# BMS.net
KiCad netlist of a schematic drawn in EAGLE
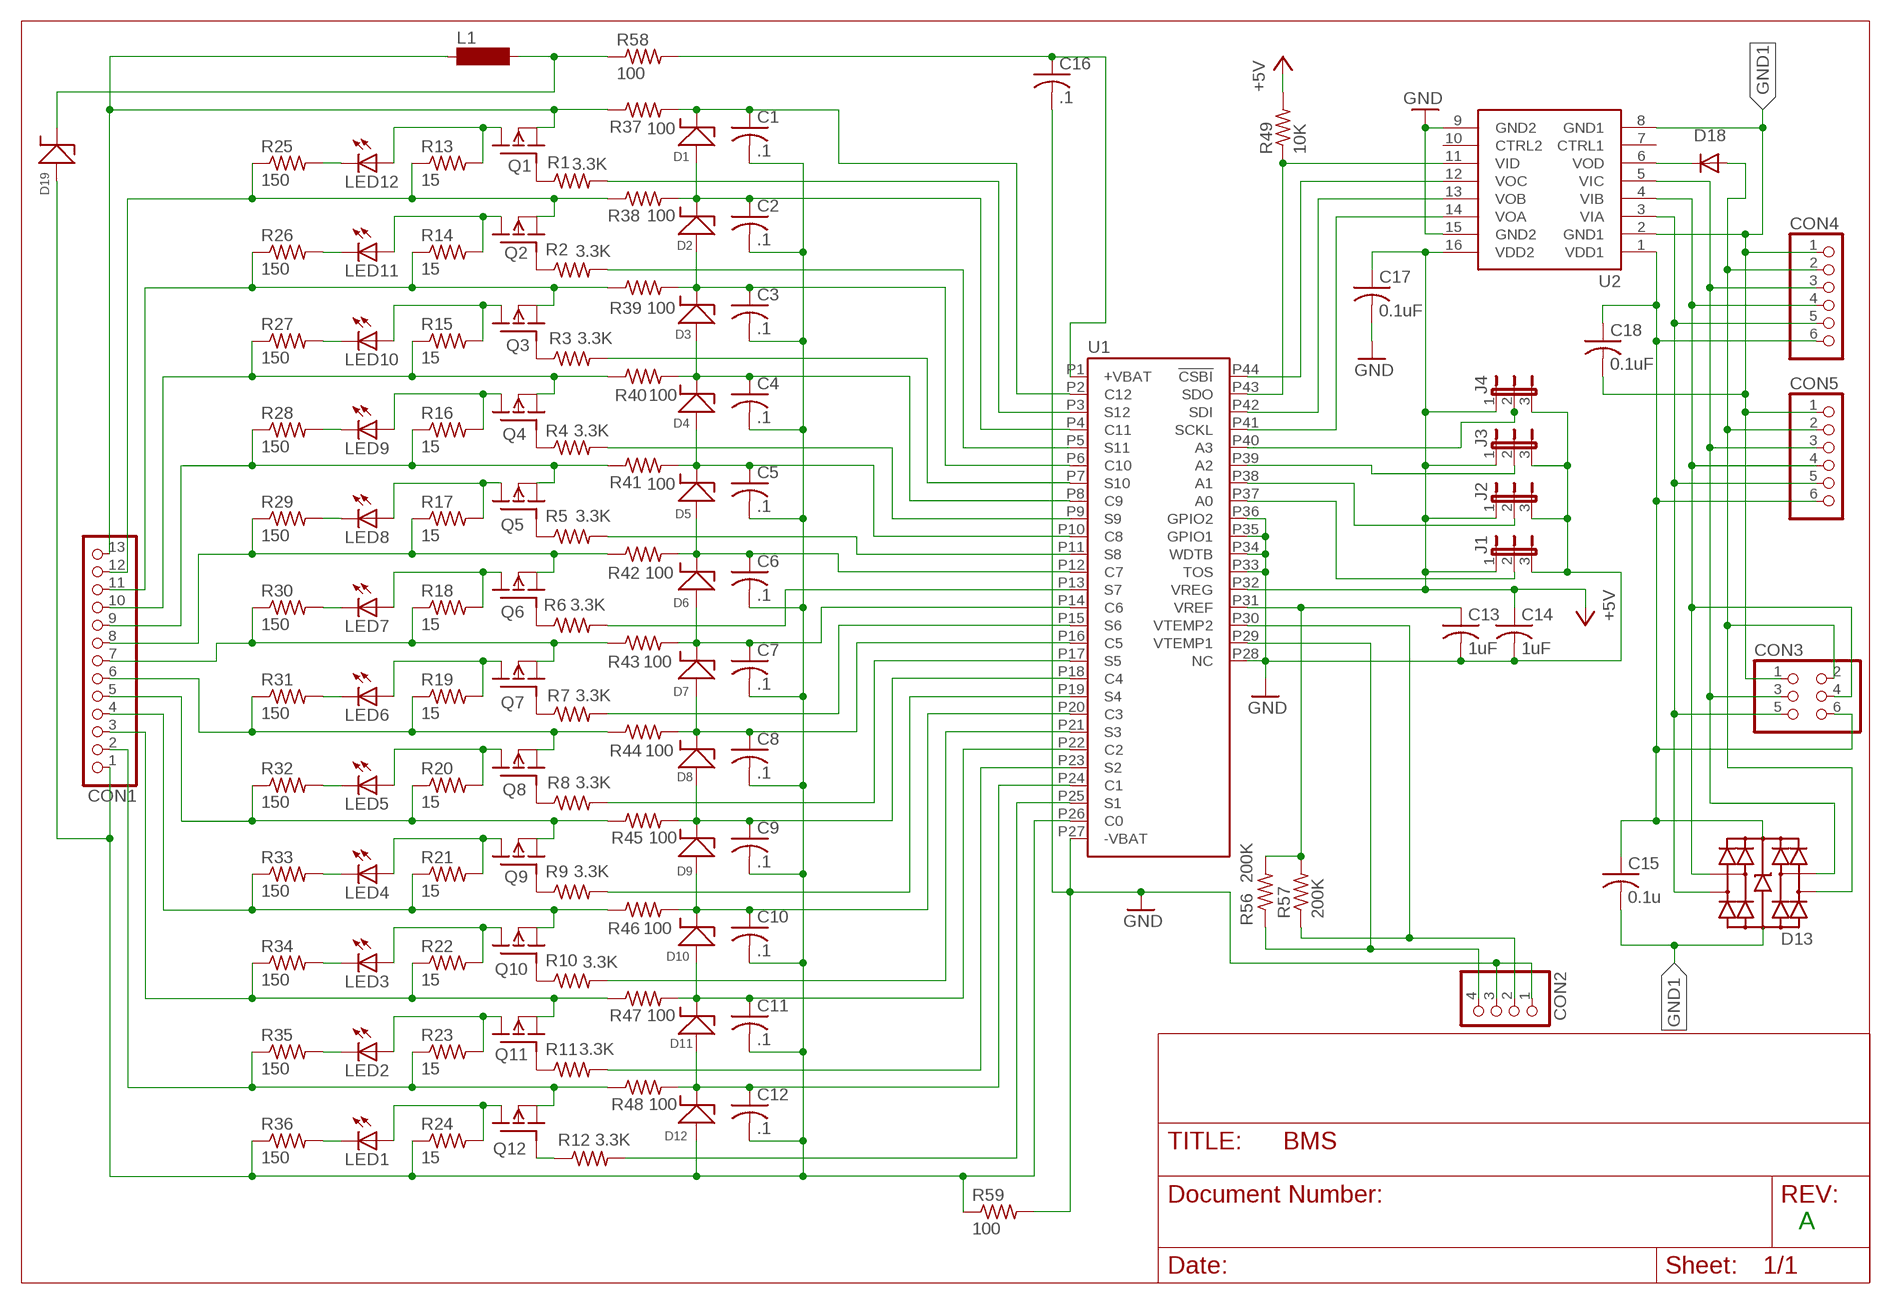
[diagram p0: schematic, sheet 1]

(export (version "E")
  (design (tool "Eeschema 10.0.6"))
  (components
    (comp (ref "C1")
      (value ".1")
      (footprint "eagle-import:C0603")
      (libsource (lib "eagle-import") (part "C-USC0603"))
    )
    (comp (ref "C2")
      (value ".1")
      (footprint "eagle-import:C0603")
      (libsource (lib "eagle-import") (part "C-USC0603"))
    )
    (comp (ref "C3")
      (value ".1")
      (footprint "eagle-import:C0603")
      (libsource (lib "eagle-import") (part "C-USC0603"))
    )
    (comp (ref "C4")
      (value ".1")
      (footprint "eagle-import:C0603")
      (libsource (lib "eagle-import") (part "C-USC0603"))
    )
    (comp (ref "C5")
      (value ".1")
      (footprint "eagle-import:C0603")
      (libsource (lib "eagle-import") (part "C-USC0603"))
    )
    (comp (ref "C6")
      (value ".1")
      (footprint "eagle-import:C0603")
      (libsource (lib "eagle-import") (part "C-USC0603"))
    )
    (comp (ref "C7")
      (value ".1")
      (footprint "eagle-import:C0603")
      (libsource (lib "eagle-import") (part "C-USC0603"))
    )
    (comp (ref "C8")
      (value ".1")
      (footprint "eagle-import:C0603")
      (libsource (lib "eagle-import") (part "C-USC0603"))
    )
    (comp (ref "C9")
      (value ".1")
      (footprint "eagle-import:C0603")
      (libsource (lib "eagle-import") (part "C-USC0603"))
    )
    (comp (ref "C10")
      (value ".1")
      (footprint "eagle-import:C0603")
      (libsource (lib "eagle-import") (part "C-USC0603"))
    )
    (comp (ref "C11")
      (value ".1")
      (footprint "eagle-import:C0603")
      (libsource (lib "eagle-import") (part "C-USC0603"))
    )
    (comp (ref "C12")
      (value ".1")
      (footprint "eagle-import:C0603")
      (libsource (lib "eagle-import") (part "C-USC0603"))
    )
    (comp (ref "C13")
      (value "1uF")
      (footprint "eagle-import:C0603")
      (libsource (lib "eagle-import") (part "C-USC0603"))
    )
    (comp (ref "C14")
      (value "1uF")
      (footprint "eagle-import:C0603")
      (libsource (lib "eagle-import") (part "C-USC0603"))
    )
    (comp (ref "C15")
      (value "0.1u")
      (footprint "eagle-import:C0603")
      (libsource (lib "eagle-import") (part "C-USC0603"))
    )
    (comp (ref "C16")
      (value ".1")
      (footprint "eagle-import:C0603")
      (libsource (lib "eagle-import") (part "C-USC0603"))
    )
    (comp (ref "C17")
      (value "0.1uF")
      (footprint "eagle-import:C0603")
      (libsource (lib "eagle-import") (part "C-USC0603"))
    )
    (comp (ref "C18")
      (value "0.1uF")
      (footprint "eagle-import:C0603")
      (libsource (lib "eagle-import") (part "C-USC0603"))
    )
    (comp (ref "CON1")
      (value "PINHD-1X13/90")
      (footprint "eagle-import:1X13_90")
      (libsource (lib "eagle-import") (part "PINHD-1X13/90"))
    )
    (comp (ref "CON2")
      (value "PINHD-1X4/90")
      (footprint "eagle-import:1X04_90")
      (libsource (lib "eagle-import") (part "PINHD-1X4/90"))
    )
    (comp (ref "CON3")
      (value "PINHD-2X3/90")
      (footprint "eagle-import:2X03_90")
      (libsource (lib "eagle-import") (part "PINHD-2X3/90"))
    )
    (comp (ref "CON4")
      (value "PINHD-1X6/90")
      (footprint "eagle-import:1X06_90")
      (libsource (lib "eagle-import") (part "PINHD-1X6/90"))
    )
    (comp (ref "CON5")
      (value "PINHD-1X6/90")
      (footprint "eagle-import:1X06_90")
      (libsource (lib "eagle-import") (part "PINHD-1X6/90"))
    )
    (comp (ref "D1")
      (value "PDZ7.5B")
      (footprint "eagle-import:SOD323")
      (libsource (lib "eagle-import") (part "PDZ7.5B"))
    )
    (comp (ref "D2")
      (value "PDZ7.5B")
      (footprint "eagle-import:SOD323")
      (libsource (lib "eagle-import") (part "PDZ7.5B"))
    )
    (comp (ref "D3")
      (value "PDZ7.5B")
      (footprint "eagle-import:SOD323")
      (libsource (lib "eagle-import") (part "PDZ7.5B"))
    )
    (comp (ref "D4")
      (value "PDZ7.5B")
      (footprint "eagle-import:SOD323")
      (libsource (lib "eagle-import") (part "PDZ7.5B"))
    )
    (comp (ref "D5")
      (value "PDZ7.5B")
      (footprint "eagle-import:SOD323")
      (libsource (lib "eagle-import") (part "PDZ7.5B"))
    )
    (comp (ref "D6")
      (value "PDZ7.5B")
      (footprint "eagle-import:SOD323")
      (libsource (lib "eagle-import") (part "PDZ7.5B"))
    )
    (comp (ref "D7")
      (value "PDZ7.5B")
      (footprint "eagle-import:SOD323")
      (libsource (lib "eagle-import") (part "PDZ7.5B"))
    )
    (comp (ref "D8")
      (value "PDZ7.5B")
      (footprint "eagle-import:SOD323")
      (libsource (lib "eagle-import") (part "PDZ7.5B"))
    )
    (comp (ref "D9")
      (value "PDZ7.5B")
      (footprint "eagle-import:SOD323")
      (libsource (lib "eagle-import") (part "PDZ7.5B"))
    )
    (comp (ref "D10")
      (value "PDZ7.5B")
      (footprint "eagle-import:SOD323")
      (libsource (lib "eagle-import") (part "PDZ7.5B"))
    )
    (comp (ref "D11")
      (value "PDZ7.5B")
      (footprint "eagle-import:SOD323")
      (libsource (lib "eagle-import") (part "PDZ7.5B"))
    )
    (comp (ref "D12")
      (value "PDZ7.5B")
      (footprint "eagle-import:SOD323")
      (libsource (lib "eagle-import") (part "PDZ7.5B"))
    )
    (comp (ref "D13")
      (value "TPD4E001DBV")
      (footprint "eagle-import:SOT23-6")
      (libsource (lib "eagle-import") (part "TPD4E001DBV"))
    )
    (comp (ref "D18")
      (value "DIODE0603")
      (footprint "eagle-import:LED-0603")
      (libsource (lib "eagle-import") (part "DIODE0603"))
    )
    (comp (ref "D19")
      (value "MMSZ5265BTIG")
      (footprint "eagle-import:SOD-123_MINI-SMA")
      (libsource (lib "eagle-import") (part "MMSZ5265BTIG"))
    )
    (comp (ref "J1")
      (value "JP2E")
      (footprint "eagle-import:JP2")
      (libsource (lib "eagle-import") (part "JP2E"))
    )
    (comp (ref "J2")
      (value "JP2E")
      (footprint "eagle-import:JP2")
      (libsource (lib "eagle-import") (part "JP2E"))
    )
    (comp (ref "J3")
      (value "JP2E")
      (footprint "eagle-import:JP2")
      (libsource (lib "eagle-import") (part "JP2E"))
    )
    (comp (ref "J4")
      (value "JP2E")
      (footprint "eagle-import:JP2")
      (libsource (lib "eagle-import") (part "JP2E"))
    )
    (comp (ref "L1")
      (value "CHOKE")
      (footprint "eagle-import:CHOKE1206")
      (libsource (lib "eagle-import") (part "CHOKE"))
    )
    (comp (ref "LED1")
      (value "LED0603")
      (footprint "eagle-import:LED-0603")
      (libsource (lib "eagle-import") (part "LED0603"))
    )
    (comp (ref "LED2")
      (value "LED0603")
      (footprint "eagle-import:LED-0603")
      (libsource (lib "eagle-import") (part "LED0603"))
    )
    (comp (ref "LED3")
      (value "LED0603")
      (footprint "eagle-import:LED-0603")
      (libsource (lib "eagle-import") (part "LED0603"))
    )
    (comp (ref "LED4")
      (value "LED0603")
      (footprint "eagle-import:LED-0603")
      (libsource (lib "eagle-import") (part "LED0603"))
    )
    (comp (ref "LED5")
      (value "LED0603")
      (footprint "eagle-import:LED-0603")
      (libsource (lib "eagle-import") (part "LED0603"))
    )
    (comp (ref "LED6")
      (value "LED0603")
      (footprint "eagle-import:LED-0603")
      (libsource (lib "eagle-import") (part "LED0603"))
    )
    (comp (ref "LED7")
      (value "LED0603")
      (footprint "eagle-import:LED-0603")
      (libsource (lib "eagle-import") (part "LED0603"))
    )
    (comp (ref "LED8")
      (value "LED0603")
      (footprint "eagle-import:LED-0603")
      (libsource (lib "eagle-import") (part "LED0603"))
    )
    (comp (ref "LED9")
      (value "LED0603")
      (footprint "eagle-import:LED-0603")
      (libsource (lib "eagle-import") (part "LED0603"))
    )
    (comp (ref "LED10")
      (value "LED0603")
      (footprint "eagle-import:LED-0603")
      (libsource (lib "eagle-import") (part "LED0603"))
    )
    (comp (ref "LED11")
      (value "LED0603")
      (footprint "eagle-import:LED-0603")
      (libsource (lib "eagle-import") (part "LED0603"))
    )
    (comp (ref "LED12")
      (value "LED0603")
      (footprint "eagle-import:LED-0603")
      (libsource (lib "eagle-import") (part "LED0603"))
    )
    (comp (ref "Q1")
      (value "FDY102PZ")
      (footprint "eagle-import:SC89-3")
      (libsource (lib "eagle-import") (part "FDY102PZ"))
    )
    (comp (ref "Q2")
      (value "FDY102PZ")
      (footprint "eagle-import:SC89-3")
      (libsource (lib "eagle-import") (part "FDY102PZ"))
    )
    (comp (ref "Q3")
      (value "FDY102PZ")
      (footprint "eagle-import:SC89-3")
      (libsource (lib "eagle-import") (part "FDY102PZ"))
    )
    (comp (ref "Q4")
      (value "FDY102PZ")
      (footprint "eagle-import:SC89-3")
      (libsource (lib "eagle-import") (part "FDY102PZ"))
    )
    (comp (ref "Q5")
      (value "FDY102PZ")
      (footprint "eagle-import:SC89-3")
      (libsource (lib "eagle-import") (part "FDY102PZ"))
    )
    (comp (ref "Q6")
      (value "FDY102PZ")
      (footprint "eagle-import:SC89-3")
      (libsource (lib "eagle-import") (part "FDY102PZ"))
    )
    (comp (ref "Q7")
      (value "FDY102PZ")
      (footprint "eagle-import:SC89-3")
      (libsource (lib "eagle-import") (part "FDY102PZ"))
    )
    (comp (ref "Q8")
      (value "FDY102PZ")
      (footprint "eagle-import:SC89-3")
      (libsource (lib "eagle-import") (part "FDY102PZ"))
    )
    (comp (ref "Q9")
      (value "FDY102PZ")
      (footprint "eagle-import:SC89-3")
      (libsource (lib "eagle-import") (part "FDY102PZ"))
    )
    (comp (ref "Q10")
      (value "FDY102PZ")
      (footprint "eagle-import:SC89-3")
      (libsource (lib "eagle-import") (part "FDY102PZ"))
    )
    (comp (ref "Q11")
      (value "FDY102PZ")
      (footprint "eagle-import:SC89-3")
      (libsource (lib "eagle-import") (part "FDY102PZ"))
    )
    (comp (ref "Q12")
      (value "FDY102PZ")
      (footprint "eagle-import:SC89-3")
      (libsource (lib "eagle-import") (part "FDY102PZ"))
    )
    (comp (ref "R1")
      (value "3.3K")
      (footprint "eagle-import:R0603")
      (libsource (lib "eagle-import") (part "R-US_R0603"))
    )
    (comp (ref "R2")
      (value "3.3K")
      (footprint "eagle-import:R0603")
      (libsource (lib "eagle-import") (part "R-US_R0603"))
    )
    (comp (ref "R3")
      (value "3.3K")
      (footprint "eagle-import:R0603")
      (libsource (lib "eagle-import") (part "R-US_R0603"))
    )
    (comp (ref "R4")
      (value "3.3K")
      (footprint "eagle-import:R0603")
      (libsource (lib "eagle-import") (part "R-US_R0603"))
    )
    (comp (ref "R5")
      (value "3.3K")
      (footprint "eagle-import:R0603")
      (libsource (lib "eagle-import") (part "R-US_R0603"))
    )
    (comp (ref "R6")
      (value "3.3K")
      (footprint "eagle-import:R0603")
      (libsource (lib "eagle-import") (part "R-US_R0603"))
    )
    (comp (ref "R7")
      (value "3.3K")
      (footprint "eagle-import:R0603")
      (libsource (lib "eagle-import") (part "R-US_R0603"))
    )
    (comp (ref "R8")
      (value "3.3K")
      (footprint "eagle-import:R0603")
      (libsource (lib "eagle-import") (part "R-US_R0603"))
    )
    (comp (ref "R9")
      (value "3.3K")
      (footprint "eagle-import:R0603")
      (libsource (lib "eagle-import") (part "R-US_R0603"))
    )
    (comp (ref "R10")
      (value "3.3K")
      (footprint "eagle-import:R0603")
      (libsource (lib "eagle-import") (part "R-US_R0603"))
    )
    (comp (ref "R11")
      (value "3.3K")
      (footprint "eagle-import:R0603")
      (libsource (lib "eagle-import") (part "R-US_R0603"))
    )
    (comp (ref "R12")
      (value "3.3K")
      (footprint "eagle-import:R0603")
      (libsource (lib "eagle-import") (part "R-US_R0603"))
    )
    (comp (ref "R13")
      (value "15")
      (footprint "eagle-import:R2512")
      (libsource (lib "eagle-import") (part "R-US_R2512"))
    )
    (comp (ref "R14")
      (value "15")
      (footprint "eagle-import:R2512")
      (libsource (lib "eagle-import") (part "R-US_R2512"))
    )
    (comp (ref "R15")
      (value "15")
      (footprint "eagle-import:R2512")
      (libsource (lib "eagle-import") (part "R-US_R2512"))
    )
    (comp (ref "R16")
      (value "15")
      (footprint "eagle-import:R2512")
      (libsource (lib "eagle-import") (part "R-US_R2512"))
    )
    (comp (ref "R17")
      (value "15")
      (footprint "eagle-import:R2512")
      (libsource (lib "eagle-import") (part "R-US_R2512"))
    )
    (comp (ref "R18")
      (value "15")
      (footprint "eagle-import:R2512")
      (libsource (lib "eagle-import") (part "R-US_R2512"))
    )
    (comp (ref "R19")
      (value "15")
      (footprint "eagle-import:R2512")
      (libsource (lib "eagle-import") (part "R-US_R2512"))
    )
    (comp (ref "R20")
      (value "15")
      (footprint "eagle-import:R2512")
      (libsource (lib "eagle-import") (part "R-US_R2512"))
    )
    (comp (ref "R21")
      (value "15")
      (footprint "eagle-import:R2512")
      (libsource (lib "eagle-import") (part "R-US_R2512"))
    )
    (comp (ref "R22")
      (value "15")
      (footprint "eagle-import:R2512")
      (libsource (lib "eagle-import") (part "R-US_R2512"))
    )
    (comp (ref "R23")
      (value "15")
      (footprint "eagle-import:R2512")
      (libsource (lib "eagle-import") (part "R-US_R2512"))
    )
    (comp (ref "R24")
      (value "15")
      (footprint "eagle-import:R2512")
      (libsource (lib "eagle-import") (part "R-US_R2512"))
    )
    (comp (ref "R25")
      (value "150")
      (footprint "eagle-import:R0603")
      (libsource (lib "eagle-import") (part "R-US_R0603"))
    )
    (comp (ref "R26")
      (value "150")
      (footprint "eagle-import:R0603")
      (libsource (lib "eagle-import") (part "R-US_R0603"))
    )
    (comp (ref "R27")
      (value "150")
      (footprint "eagle-import:R0603")
      (libsource (lib "eagle-import") (part "R-US_R0603"))
    )
    (comp (ref "R28")
      (value "150")
      (footprint "eagle-import:R0603")
      (libsource (lib "eagle-import") (part "R-US_R0603"))
    )
    (comp (ref "R29")
      (value "150")
      (footprint "eagle-import:R0603")
      (libsource (lib "eagle-import") (part "R-US_R0603"))
    )
    (comp (ref "R30")
      (value "150")
      (footprint "eagle-import:R0603")
      (libsource (lib "eagle-import") (part "R-US_R0603"))
    )
    (comp (ref "R31")
      (value "150")
      (footprint "eagle-import:R0603")
      (libsource (lib "eagle-import") (part "R-US_R0603"))
    )
    (comp (ref "R32")
      (value "150")
      (footprint "eagle-import:R0603")
      (libsource (lib "eagle-import") (part "R-US_R0603"))
    )
    (comp (ref "R33")
      (value "150")
      (footprint "eagle-import:R0603")
      (libsource (lib "eagle-import") (part "R-US_R0603"))
    )
    (comp (ref "R34")
      (value "150")
      (footprint "eagle-import:R0603")
      (libsource (lib "eagle-import") (part "R-US_R0603"))
    )
    (comp (ref "R35")
      (value "150")
      (footprint "eagle-import:R0603")
      (libsource (lib "eagle-import") (part "R-US_R0603"))
    )
    (comp (ref "R36")
      (value "150")
      (footprint "eagle-import:R0603")
      (libsource (lib "eagle-import") (part "R-US_R0603"))
    )
    (comp (ref "R37")
      (value "100")
      (footprint "eagle-import:R0603")
      (libsource (lib "eagle-import") (part "R-US_R0603"))
    )
    (comp (ref "R38")
      (value "100")
      (footprint "eagle-import:R0603")
      (libsource (lib "eagle-import") (part "R-US_R0603"))
    )
    (comp (ref "R39")
      (value "100")
      (footprint "eagle-import:R0603")
      (libsource (lib "eagle-import") (part "R-US_R0603"))
    )
    (comp (ref "R40")
      (value "100")
      (footprint "eagle-import:R0603")
      (libsource (lib "eagle-import") (part "R-US_R0603"))
    )
    (comp (ref "R41")
      (value "100")
      (footprint "eagle-import:R0603")
      (libsource (lib "eagle-import") (part "R-US_R0603"))
    )
    (comp (ref "R42")
      (value "100")
      (footprint "eagle-import:R0603")
      (libsource (lib "eagle-import") (part "R-US_R0603"))
    )
    (comp (ref "R43")
      (value "100")
      (footprint "eagle-import:R0603")
      (libsource (lib "eagle-import") (part "R-US_R0603"))
    )
    (comp (ref "R44")
      (value "100")
      (footprint "eagle-import:R0603")
      (libsource (lib "eagle-import") (part "R-US_R0603"))
    )
    (comp (ref "R45")
      (value "100")
      (footprint "eagle-import:R0603")
      (libsource (lib "eagle-import") (part "R-US_R0603"))
    )
    (comp (ref "R46")
      (value "100")
      (footprint "eagle-import:R0603")
      (libsource (lib "eagle-import") (part "R-US_R0603"))
    )
    (comp (ref "R47")
      (value "100")
      (footprint "eagle-import:R0603")
      (libsource (lib "eagle-import") (part "R-US_R0603"))
    )
    (comp (ref "R48")
      (value "100")
      (footprint "eagle-import:R0603")
      (libsource (lib "eagle-import") (part "R-US_R0603"))
    )
    (comp (ref "R49")
      (value "10K")
      (footprint "eagle-import:R0603")
      (libsource (lib "eagle-import") (part "R-US_R0603"))
    )
    (comp (ref "R56")
      (value "200K")
      (footprint "eagle-import:R0603")
      (libsource (lib "eagle-import") (part "R-US_R0603"))
    )
    (comp (ref "R57")
      (value "200K")
      (footprint "eagle-import:R0603")
      (libsource (lib "eagle-import") (part "R-US_R0603"))
    )
    (comp (ref "R58")
      (value "100")
      (footprint "eagle-import:R0603")
      (libsource (lib "eagle-import") (part "R-US_R0603"))
    )
    (comp (ref "R59")
      (value "100")
      (footprint "eagle-import:R0603")
      (libsource (lib "eagle-import") (part "R-US_R0603"))
    )
    (comp (ref "U1")
      (value "LTC6803-2")
      (footprint "eagle-import:SSOP44")
      (fields (field (name "PARTNUM") "LTC6803IG-2#PBF"))
      (libsource (lib "eagle-import") (part "LTC6803-2"))
    )
    (comp (ref "U2")
      (value "ADUM1411RW")
      (footprint "eagle-import:SO16W")
      (fields (field (name "PARTNUM") "ADuM1411A"))
      (libsource (lib "eagle-import") (part "ADUM1411RW"))
    )
  )
  (nets
    (net (code "1") (name "+5V") (class "Default")
      (node (ref "C14") (pin "1") (pinfunction "1_1") (pintype "passive"))
      (node (ref "C17") (pin "1") (pinfunction "1_1") (pintype "passive"))
      (node (ref "J1") (pin "1") (pinfunction "1_1") (pintype "passive"))
      (node (ref "J2") (pin "1") (pinfunction "1_1") (pintype "passive"))
      (node (ref "J3") (pin "1") (pinfunction "1_1") (pintype "passive"))
      (node (ref "J4") (pin "1") (pinfunction "1_1") (pintype "passive"))
      (node (ref "R49") (pin "2") (pinfunction "2_2") (pintype "passive"))
      (node (ref "U1") (pin "P32") (pinfunction "VREG_P32") (pintype "passive"))
      (node (ref "U2") (pin "16") (pinfunction "VDD2_16") (pintype "passive"))
    )
    (net (code "2") (name "GND") (class "Default")
      (node (ref "C13") (pin "2") (pinfunction "2_2") (pintype "passive"))
      (node (ref "C14") (pin "2") (pinfunction "2_2") (pintype "passive"))
      (node (ref "C16") (pin "2") (pinfunction "2_2") (pintype "passive"))
      (node (ref "C17") (pin "2") (pinfunction "2_2") (pintype "passive"))
      (node (ref "CON2") (pin "1") (pinfunction "1_1") (pintype "passive"))
      (node (ref "CON2") (pin "3") (pinfunction "3_3") (pintype "passive"))
      (node (ref "J1") (pin "3") (pinfunction "3_3") (pintype "passive"))
      (node (ref "J2") (pin "3") (pinfunction "3_3") (pintype "passive"))
      (node (ref "J3") (pin "3") (pinfunction "3_3") (pintype "passive"))
      (node (ref "J4") (pin "3") (pinfunction "3_3") (pintype "passive"))
      (node (ref "R59") (pin "2") (pinfunction "2_2") (pintype "passive"))
      (node (ref "U1") (pin "P27") (pinfunction "-VBAT_P27") (pintype "passive"))
      (node (ref "U1") (pin "P28") (pinfunction "NC_P28") (pintype "passive"))
      (node (ref "U1") (pin "P33") (pinfunction "TOS_P33") (pintype "passive"))
      (node (ref "U1") (pin "P34") (pinfunction "WDTB_P34") (pintype "passive"))
      (node (ref "U1") (pin "P35") (pinfunction "GPIO1_P35") (pintype "passive"))
      (node (ref "U1") (pin "P36") (pinfunction "GPIO2_P36") (pintype "passive"))
      (node (ref "U2") (pin "15") (pinfunction "GND2_15") (pintype "passive"))
      (node (ref "U2") (pin "9") (pinfunction "GND2_9") (pintype "passive"))
    )
    (net (code "3") (name "GND1") (class "Default")
      (node (ref "C15") (pin "2") (pinfunction "2_2") (pintype "passive"))
      (node (ref "C18") (pin "2") (pinfunction "2_2") (pintype "passive"))
      (node (ref "CON3") (pin "1") (pinfunction "1_1") (pintype "passive"))
      (node (ref "CON4") (pin "1") (pinfunction "1_1") (pintype "passive"))
      (node (ref "CON5") (pin "1") (pinfunction "1_1") (pintype "passive"))
      (node (ref "D13") (pin "2") (pinfunction "GND_2") (pintype "passive"))
      (node (ref "U2") (pin "2") (pinfunction "GND1_2") (pintype "passive"))
      (node (ref "U2") (pin "8") (pinfunction "GND1_8") (pintype "passive"))
    )
    (net (code "4") (name "Net-(D1-1)") (class "Default")
      (node (ref "C1") (pin "1") (pinfunction "1_1") (pintype "passive"))
      (node (ref "D1") (pin "P$1") (pinfunction "1_P$1") (pintype "passive"))
      (node (ref "R37") (pin "2") (pinfunction "2_2") (pintype "passive"))
      (node (ref "U1") (pin "P2") (pinfunction "C12_P2") (pintype "passive"))
    )
    (net (code "5") (name "Net-(D1-2)") (class "Default")
      (node (ref "C2") (pin "1") (pinfunction "1_1") (pintype "passive"))
      (node (ref "D1") (pin "P$2") (pinfunction "2_P$2") (pintype "passive"))
      (node (ref "D2") (pin "P$1") (pinfunction "1_P$1") (pintype "passive"))
      (node (ref "R38") (pin "2") (pinfunction "2_2") (pintype "passive"))
      (node (ref "U1") (pin "P4") (pinfunction "C11_P4") (pintype "passive"))
    )
    (net (code "6") (name "Net-(D2-2)") (class "Default")
      (node (ref "C3") (pin "1") (pinfunction "1_1") (pintype "passive"))
      (node (ref "D2") (pin "P$2") (pinfunction "2_P$2") (pintype "passive"))
      (node (ref "D3") (pin "P$1") (pinfunction "1_P$1") (pintype "passive"))
      (node (ref "R39") (pin "2") (pinfunction "2_2") (pintype "passive"))
      (node (ref "U1") (pin "P6") (pinfunction "C10_P6") (pintype "passive"))
    )
    (net (code "7") (name "Net-(D3-2)") (class "Default")
      (node (ref "C4") (pin "1") (pinfunction "1_1") (pintype "passive"))
      (node (ref "D3") (pin "P$2") (pinfunction "2_P$2") (pintype "passive"))
      (node (ref "D4") (pin "P$1") (pinfunction "1_P$1") (pintype "passive"))
      (node (ref "R40") (pin "2") (pinfunction "2_2") (pintype "passive"))
      (node (ref "U1") (pin "P8") (pinfunction "C9_P8") (pintype "passive"))
    )
    (net (code "8") (name "Net-(D4-2)") (class "Default")
      (node (ref "C5") (pin "1") (pinfunction "1_1") (pintype "passive"))
      (node (ref "D4") (pin "P$2") (pinfunction "2_P$2") (pintype "passive"))
      (node (ref "D5") (pin "P$1") (pinfunction "1_P$1") (pintype "passive"))
      (node (ref "R41") (pin "2") (pinfunction "2_2") (pintype "passive"))
      (node (ref "U1") (pin "P10") (pinfunction "C8_P10") (pintype "passive"))
    )
    (net (code "9") (name "Net-(D5-2)") (class "Default")
      (node (ref "C6") (pin "1") (pinfunction "1_1") (pintype "passive"))
      (node (ref "D5") (pin "P$2") (pinfunction "2_P$2") (pintype "passive"))
      (node (ref "D6") (pin "P$1") (pinfunction "1_P$1") (pintype "passive"))
      (node (ref "R42") (pin "2") (pinfunction "2_2") (pintype "passive"))
      (node (ref "U1") (pin "P12") (pinfunction "C7_P12") (pintype "passive"))
    )
    (net (code "10") (name "Net-(D6-2)") (class "Default")
      (node (ref "C7") (pin "1") (pinfunction "1_1") (pintype "passive"))
      (node (ref "D6") (pin "P$2") (pinfunction "2_P$2") (pintype "passive"))
      (node (ref "D7") (pin "P$1") (pinfunction "1_P$1") (pintype "passive"))
      (node (ref "R43") (pin "2") (pinfunction "2_2") (pintype "passive"))
      (node (ref "U1") (pin "P14") (pinfunction "C6_P14") (pintype "passive"))
    )
    (net (code "11") (name "Net-(D7-2)") (class "Default")
      (node (ref "C8") (pin "1") (pinfunction "1_1") (pintype "passive"))
      (node (ref "D7") (pin "P$2") (pinfunction "2_P$2") (pintype "passive"))
      (node (ref "D8") (pin "P$1") (pinfunction "1_P$1") (pintype "passive"))
      (node (ref "R44") (pin "2") (pinfunction "2_2") (pintype "passive"))
      (node (ref "U1") (pin "P16") (pinfunction "C5_P16") (pintype "passive"))
    )
    (net (code "12") (name "Net-(D8-2)") (class "Default")
      (node (ref "C9") (pin "1") (pinfunction "1_1") (pintype "passive"))
      (node (ref "D8") (pin "P$2") (pinfunction "2_P$2") (pintype "passive"))
      (node (ref "D9") (pin "P$1") (pinfunction "1_P$1") (pintype "passive"))
      (node (ref "R45") (pin "2") (pinfunction "2_2") (pintype "passive"))
      (node (ref "U1") (pin "P18") (pinfunction "C4_P18") (pintype "passive"))
    )
    (net (code "13") (name "Net-(D10-1)") (class "Default")
      (node (ref "C10") (pin "1") (pinfunction "1_1") (pintype "passive"))
      (node (ref "D10") (pin "P$1") (pinfunction "1_P$1") (pintype "passive"))
      (node (ref "D9") (pin "P$2") (pinfunction "2_P$2") (pintype "passive"))
      (node (ref "R46") (pin "2") (pinfunction "2_2") (pintype "passive"))
      (node (ref "U1") (pin "P20") (pinfunction "C3_P20") (pintype "passive"))
    )
    (net (code "14") (name "Net-(D10-2)") (class "Default")
      (node (ref "C11") (pin "1") (pinfunction "1_1") (pintype "passive"))
      (node (ref "D10") (pin "P$2") (pinfunction "2_P$2") (pintype "passive"))
      (node (ref "D11") (pin "P$1") (pinfunction "1_P$1") (pintype "passive"))
      (node (ref "R47") (pin "2") (pinfunction "2_2") (pintype "passive"))
      (node (ref "U1") (pin "P22") (pinfunction "C2_P22") (pintype "passive"))
    )
    (net (code "15") (name "Net-(D11-2)") (class "Default")
      (node (ref "C12") (pin "1") (pinfunction "1_1") (pintype "passive"))
      (node (ref "D11") (pin "P$2") (pinfunction "2_P$2") (pintype "passive"))
      (node (ref "D12") (pin "P$1") (pinfunction "1_P$1") (pintype "passive"))
      (node (ref "R48") (pin "2") (pinfunction "2_2") (pintype "passive"))
      (node (ref "U1") (pin "P24") (pinfunction "C1_P24") (pintype "passive"))
    )
    (net (code "16") (name "Net-(D12-2)") (class "Default")
      (node (ref "C1") (pin "2") (pinfunction "2_2") (pintype "passive"))
      (node (ref "C10") (pin "2") (pinfunction "2_2") (pintype "passive"))
      (node (ref "C11") (pin "2") (pinfunction "2_2") (pintype "passive"))
      (node (ref "C12") (pin "2") (pinfunction "2_2") (pintype "passive"))
      (node (ref "C2") (pin "2") (pinfunction "2_2") (pintype "passive"))
      (node (ref "C3") (pin "2") (pinfunction "2_2") (pintype "passive"))
      (node (ref "C4") (pin "2") (pinfunction "2_2") (pintype "passive"))
      (node (ref "C5") (pin "2") (pinfunction "2_2") (pintype "passive"))
      (node (ref "C6") (pin "2") (pinfunction "2_2") (pintype "passive"))
      (node (ref "C7") (pin "2") (pinfunction "2_2") (pintype "passive"))
      (node (ref "C8") (pin "2") (pinfunction "2_2") (pintype "passive"))
      (node (ref "C9") (pin "2") (pinfunction "2_2") (pintype "passive"))
      (node (ref "CON1") (pin "1") (pinfunction "1_1") (pintype "passive"))
      (node (ref "D12") (pin "P$2") (pinfunction "2_P$2") (pintype "passive"))
      (node (ref "D19") (pin "A") (pinfunction "2_A") (pintype "passive"))
      (node (ref "R24") (pin "1") (pinfunction "1_1") (pintype "passive"))
      (node (ref "R36") (pin "1") (pinfunction "1_1") (pintype "passive"))
      (node (ref "R59") (pin "1") (pinfunction "1_1") (pintype "passive"))
      (node (ref "U1") (pin "P26") (pinfunction "C0_P26") (pintype "passive"))
    )
    (net (code "17") (name "Net-(D13-IO1)") (class "Default")
      (node (ref "CON3") (pin "5") (pinfunction "5_5") (pintype "passive"))
      (node (ref "CON4") (pin "5") (pinfunction "5_5") (pintype "passive"))
      (node (ref "CON5") (pin "5") (pinfunction "5_5") (pintype "passive"))
      (node (ref "D13") (pin "1") (pinfunction "IO1_1") (pintype "passive"))
      (node (ref "U2") (pin "3") (pinfunction "VIA_3") (pintype "passive"))
    )
    (net (code "18") (name "Net-(D13-IO2)") (class "Default")
      (node (ref "CON3") (pin "4") (pinfunction "4_4") (pintype "passive"))
      (node (ref "CON4") (pin "4") (pinfunction "4_4") (pintype "passive"))
      (node (ref "CON5") (pin "4") (pinfunction "4_4") (pintype "passive"))
      (node (ref "D13") (pin "3") (pinfunction "IO2_3") (pintype "passive"))
      (node (ref "U2") (pin "4") (pinfunction "VIB_4") (pintype "passive"))
    )
    (net (code "19") (name "Net-(D13-IO3)") (class "Default")
      (node (ref "CON3") (pin "3") (pinfunction "3_3") (pintype "passive"))
      (node (ref "CON4") (pin "3") (pinfunction "3_3") (pintype "passive"))
      (node (ref "CON5") (pin "3") (pinfunction "3_3") (pintype "passive"))
      (node (ref "D13") (pin "4") (pinfunction "IO3_4") (pintype "passive"))
      (node (ref "U2") (pin "5") (pinfunction "VIC_5") (pintype "passive"))
    )
    (net (code "20") (name "Net-(D13-IO4)") (class "Default")
      (node (ref "CON3") (pin "2") (pinfunction "2_2") (pintype "passive"))
      (node (ref "CON4") (pin "2") (pinfunction "2_2") (pintype "passive"))
      (node (ref "CON5") (pin "2") (pinfunction "2_2") (pintype "passive"))
      (node (ref "D13") (pin "6") (pinfunction "IO4_6") (pintype "passive"))
      (node (ref "D18") (pin "A") (pinfunction "A_A") (pintype "passive"))
    )
    (net (code "21") (name "Net-(D13-VCC)") (class "Default")
      (node (ref "C15") (pin "1") (pinfunction "1_1") (pintype "passive"))
      (node (ref "C18") (pin "1") (pinfunction "1_1") (pintype "passive"))
      (node (ref "CON3") (pin "6") (pinfunction "6_6") (pintype "passive"))
      (node (ref "CON4") (pin "6") (pinfunction "6_6") (pintype "passive"))
      (node (ref "CON5") (pin "6") (pinfunction "6_6") (pintype "passive"))
      (node (ref "D13") (pin "5") (pinfunction "VCC_5") (pintype "passive"))
      (node (ref "U2") (pin "1") (pinfunction "VDD1_1") (pintype "passive"))
    )
    (net (code "22") (name "Net-(D19-1)") (class "Default")
      (node (ref "D19") (pin "C") (pinfunction "1_C") (pintype "passive"))
      (node (ref "L1") (pin "2") (pinfunction "2_2") (pintype "passive"))
      (node (ref "R58") (pin "1") (pinfunction "1_1") (pintype "passive"))
    )
    (net (code "23") (name "Net-(LED1-PadC)") (class "Default")
      (node (ref "LED1") (pin "C") (pinfunction "C_C") (pintype "passive"))
      (node (ref "R36") (pin "2") (pinfunction "2_2") (pintype "passive"))
    )
    (net (code "24") (name "Net-(LED2-PadC)") (class "Default")
      (node (ref "LED2") (pin "C") (pinfunction "C_C") (pintype "passive"))
      (node (ref "R35") (pin "2") (pinfunction "2_2") (pintype "passive"))
    )
    (net (code "25") (name "Net-(LED3-PadC)") (class "Default")
      (node (ref "LED3") (pin "C") (pinfunction "C_C") (pintype "passive"))
      (node (ref "R34") (pin "2") (pinfunction "2_2") (pintype "passive"))
    )
    (net (code "26") (name "Net-(LED4-PadC)") (class "Default")
      (node (ref "LED4") (pin "C") (pinfunction "C_C") (pintype "passive"))
      (node (ref "R33") (pin "2") (pinfunction "2_2") (pintype "passive"))
    )
    (net (code "27") (name "Net-(LED5-PadC)") (class "Default")
      (node (ref "LED5") (pin "C") (pinfunction "C_C") (pintype "passive"))
      (node (ref "R32") (pin "2") (pinfunction "2_2") (pintype "passive"))
    )
    (net (code "28") (name "Net-(LED6-PadC)") (class "Default")
      (node (ref "LED6") (pin "C") (pinfunction "C_C") (pintype "passive"))
      (node (ref "R31") (pin "2") (pinfunction "2_2") (pintype "passive"))
    )
    (net (code "29") (name "Net-(LED7-PadC)") (class "Default")
      (node (ref "LED7") (pin "C") (pinfunction "C_C") (pintype "passive"))
      (node (ref "R30") (pin "2") (pinfunction "2_2") (pintype "passive"))
    )
    (net (code "30") (name "Net-(LED8-PadC)") (class "Default")
      (node (ref "LED8") (pin "C") (pinfunction "C_C") (pintype "passive"))
      (node (ref "R29") (pin "2") (pinfunction "2_2") (pintype "passive"))
    )
    (net (code "31") (name "Net-(LED9-PadC)") (class "Default")
      (node (ref "LED9") (pin "C") (pinfunction "C_C") (pintype "passive"))
      (node (ref "R28") (pin "2") (pinfunction "2_2") (pintype "passive"))
    )
    (net (code "32") (name "Net-(LED10-PadC)") (class "Default")
      (node (ref "LED10") (pin "C") (pinfunction "C_C") (pintype "passive"))
      (node (ref "R27") (pin "2") (pinfunction "2_2") (pintype "passive"))
    )
    (net (code "33") (name "Net-(LED11-PadC)") (class "Default")
      (node (ref "LED11") (pin "C") (pinfunction "C_C") (pintype "passive"))
      (node (ref "R26") (pin "2") (pinfunction "2_2") (pintype "passive"))
    )
    (net (code "34") (name "Net-(LED12-PadC)") (class "Default")
      (node (ref "LED12") (pin "C") (pinfunction "C_C") (pintype "passive"))
      (node (ref "R25") (pin "2") (pinfunction "2_2") (pintype "passive"))
    )
    (net (code "35") (name "Net-(Q1-D)") (class "Default")
      (node (ref "LED12") (pin "A") (pinfunction "A_A") (pintype "passive"))
      (node (ref "Q1") (pin "P$3") (pinfunction "D_P$3") (pintype "passive"))
      (node (ref "R13") (pin "2") (pinfunction "2_2") (pintype "passive"))
    )
    (net (code "36") (name "Net-(Q1-G)") (class "Default")
      (node (ref "Q1") (pin "P$1") (pinfunction "G_P$1") (pintype "passive"))
      (node (ref "R1") (pin "1") (pinfunction "1_1") (pintype "passive"))
    )
    (net (code "37") (name "Net-(Q1-S)") (class "Default")
      (node (ref "CON1") (pin "13") (pinfunction "13_13") (pintype "passive"))
      (node (ref "L1") (pin "1") (pinfunction "1_1") (pintype "passive"))
      (node (ref "Q1") (pin "P$2") (pinfunction "S_P$2") (pintype "passive"))
      (node (ref "R37") (pin "1") (pinfunction "1_1") (pintype "passive"))
    )
    (net (code "38") (name "Net-(Q2-D)") (class "Default")
      (node (ref "LED11") (pin "A") (pinfunction "A_A") (pintype "passive"))
      (node (ref "Q2") (pin "P$3") (pinfunction "D_P$3") (pintype "passive"))
      (node (ref "R14") (pin "2") (pinfunction "2_2") (pintype "passive"))
    )
    (net (code "39") (name "Net-(Q2-G)") (class "Default")
      (node (ref "Q2") (pin "P$1") (pinfunction "G_P$1") (pintype "passive"))
      (node (ref "R2") (pin "1") (pinfunction "1_1") (pintype "passive"))
    )
    (net (code "40") (name "Net-(Q2-S)") (class "Default")
      (node (ref "CON1") (pin "12") (pinfunction "12_12") (pintype "passive"))
      (node (ref "Q2") (pin "P$2") (pinfunction "S_P$2") (pintype "passive"))
      (node (ref "R13") (pin "1") (pinfunction "1_1") (pintype "passive"))
      (node (ref "R25") (pin "1") (pinfunction "1_1") (pintype "passive"))
      (node (ref "R38") (pin "1") (pinfunction "1_1") (pintype "passive"))
    )
    (net (code "41") (name "Net-(Q3-D)") (class "Default")
      (node (ref "LED10") (pin "A") (pinfunction "A_A") (pintype "passive"))
      (node (ref "Q3") (pin "P$3") (pinfunction "D_P$3") (pintype "passive"))
      (node (ref "R15") (pin "2") (pinfunction "2_2") (pintype "passive"))
    )
    (net (code "42") (name "Net-(Q3-G)") (class "Default")
      (node (ref "Q3") (pin "P$1") (pinfunction "G_P$1") (pintype "passive"))
      (node (ref "R3") (pin "1") (pinfunction "1_1") (pintype "passive"))
    )
    (net (code "43") (name "Net-(Q3-S)") (class "Default")
      (node (ref "CON1") (pin "11") (pinfunction "11_11") (pintype "passive"))
      (node (ref "Q3") (pin "P$2") (pinfunction "S_P$2") (pintype "passive"))
      (node (ref "R14") (pin "1") (pinfunction "1_1") (pintype "passive"))
      (node (ref "R26") (pin "1") (pinfunction "1_1") (pintype "passive"))
      (node (ref "R39") (pin "1") (pinfunction "1_1") (pintype "passive"))
    )
    (net (code "44") (name "Net-(Q4-D)") (class "Default")
      (node (ref "LED9") (pin "A") (pinfunction "A_A") (pintype "passive"))
      (node (ref "Q4") (pin "P$3") (pinfunction "D_P$3") (pintype "passive"))
      (node (ref "R16") (pin "2") (pinfunction "2_2") (pintype "passive"))
    )
    (net (code "45") (name "Net-(Q4-G)") (class "Default")
      (node (ref "Q4") (pin "P$1") (pinfunction "G_P$1") (pintype "passive"))
      (node (ref "R4") (pin "1") (pinfunction "1_1") (pintype "passive"))
    )
    (net (code "46") (name "Net-(Q4-S)") (class "Default")
      (node (ref "CON1") (pin "10") (pinfunction "10_10") (pintype "passive"))
      (node (ref "Q4") (pin "P$2") (pinfunction "S_P$2") (pintype "passive"))
      (node (ref "R15") (pin "1") (pinfunction "1_1") (pintype "passive"))
      (node (ref "R27") (pin "1") (pinfunction "1_1") (pintype "passive"))
      (node (ref "R40") (pin "1") (pinfunction "1_1") (pintype "passive"))
    )
    (net (code "47") (name "Net-(Q5-D)") (class "Default")
      (node (ref "LED8") (pin "A") (pinfunction "A_A") (pintype "passive"))
      (node (ref "Q5") (pin "P$3") (pinfunction "D_P$3") (pintype "passive"))
      (node (ref "R17") (pin "2") (pinfunction "2_2") (pintype "passive"))
    )
    (net (code "48") (name "Net-(Q5-G)") (class "Default")
      (node (ref "Q5") (pin "P$1") (pinfunction "G_P$1") (pintype "passive"))
      (node (ref "R5") (pin "1") (pinfunction "1_1") (pintype "passive"))
    )
    (net (code "49") (name "Net-(Q5-S)") (class "Default")
      (node (ref "CON1") (pin "9") (pinfunction "9_9") (pintype "passive"))
      (node (ref "Q5") (pin "P$2") (pinfunction "S_P$2") (pintype "passive"))
      (node (ref "R16") (pin "1") (pinfunction "1_1") (pintype "passive"))
      (node (ref "R28") (pin "1") (pinfunction "1_1") (pintype "passive"))
      (node (ref "R41") (pin "1") (pinfunction "1_1") (pintype "passive"))
    )
    (net (code "50") (name "Net-(Q6-D)") (class "Default")
      (node (ref "LED7") (pin "A") (pinfunction "A_A") (pintype "passive"))
      (node (ref "Q6") (pin "P$3") (pinfunction "D_P$3") (pintype "passive"))
      (node (ref "R18") (pin "2") (pinfunction "2_2") (pintype "passive"))
    )
    (net (code "51") (name "Net-(Q6-G)") (class "Default")
      (node (ref "Q6") (pin "P$1") (pinfunction "G_P$1") (pintype "passive"))
      (node (ref "R6") (pin "1") (pinfunction "1_1") (pintype "passive"))
    )
    (net (code "52") (name "Net-(Q6-S)") (class "Default")
      (node (ref "CON1") (pin "8") (pinfunction "8_8") (pintype "passive"))
      (node (ref "Q6") (pin "P$2") (pinfunction "S_P$2") (pintype "passive"))
      (node (ref "R17") (pin "1") (pinfunction "1_1") (pintype "passive"))
      (node (ref "R29") (pin "1") (pinfunction "1_1") (pintype "passive"))
      (node (ref "R42") (pin "1") (pinfunction "1_1") (pintype "passive"))
    )
    (net (code "53") (name "Net-(Q7-D)") (class "Default")
      (node (ref "LED6") (pin "A") (pinfunction "A_A") (pintype "passive"))
      (node (ref "Q7") (pin "P$3") (pinfunction "D_P$3") (pintype "passive"))
      (node (ref "R19") (pin "2") (pinfunction "2_2") (pintype "passive"))
    )
    (net (code "54") (name "Net-(Q7-G)") (class "Default")
      (node (ref "Q7") (pin "P$1") (pinfunction "G_P$1") (pintype "passive"))
      (node (ref "R7") (pin "1") (pinfunction "1_1") (pintype "passive"))
    )
    (net (code "55") (name "Net-(Q7-S)") (class "Default")
      (node (ref "CON1") (pin "7") (pinfunction "7_7") (pintype "passive"))
      (node (ref "Q7") (pin "P$2") (pinfunction "S_P$2") (pintype "passive"))
      (node (ref "R18") (pin "1") (pinfunction "1_1") (pintype "passive"))
      (node (ref "R30") (pin "1") (pinfunction "1_1") (pintype "passive"))
      (node (ref "R43") (pin "1") (pinfunction "1_1") (pintype "passive"))
    )
    (net (code "56") (name "Net-(Q8-D)") (class "Default")
      (node (ref "LED5") (pin "A") (pinfunction "A_A") (pintype "passive"))
      (node (ref "Q8") (pin "P$3") (pinfunction "D_P$3") (pintype "passive"))
      (node (ref "R20") (pin "2") (pinfunction "2_2") (pintype "passive"))
    )
    (net (code "57") (name "Net-(Q8-G)") (class "Default")
      (node (ref "Q8") (pin "P$1") (pinfunction "G_P$1") (pintype "passive"))
      (node (ref "R8") (pin "1") (pinfunction "1_1") (pintype "passive"))
    )
    (net (code "58") (name "Net-(Q8-S)") (class "Default")
      (node (ref "CON1") (pin "6") (pinfunction "6_6") (pintype "passive"))
      (node (ref "Q8") (pin "P$2") (pinfunction "S_P$2") (pintype "passive"))
      (node (ref "R19") (pin "1") (pinfunction "1_1") (pintype "passive"))
      (node (ref "R31") (pin "1") (pinfunction "1_1") (pintype "passive"))
      (node (ref "R44") (pin "1") (pinfunction "1_1") (pintype "passive"))
    )
    (net (code "59") (name "Net-(Q9-D)") (class "Default")
      (node (ref "LED4") (pin "A") (pinfunction "A_A") (pintype "passive"))
      (node (ref "Q9") (pin "P$3") (pinfunction "D_P$3") (pintype "passive"))
      (node (ref "R21") (pin "2") (pinfunction "2_2") (pintype "passive"))
    )
    (net (code "60") (name "Net-(Q9-G)") (class "Default")
      (node (ref "Q9") (pin "P$1") (pinfunction "G_P$1") (pintype "passive"))
      (node (ref "R9") (pin "1") (pinfunction "1_1") (pintype "passive"))
    )
    (net (code "61") (name "Net-(Q9-S)") (class "Default")
      (node (ref "CON1") (pin "5") (pinfunction "5_5") (pintype "passive"))
      (node (ref "Q9") (pin "P$2") (pinfunction "S_P$2") (pintype "passive"))
      (node (ref "R20") (pin "1") (pinfunction "1_1") (pintype "passive"))
      (node (ref "R32") (pin "1") (pinfunction "1_1") (pintype "passive"))
      (node (ref "R45") (pin "1") (pinfunction "1_1") (pintype "passive"))
    )
    (net (code "62") (name "Net-(Q10-D)") (class "Default")
      (node (ref "LED3") (pin "A") (pinfunction "A_A") (pintype "passive"))
      (node (ref "Q10") (pin "P$3") (pinfunction "D_P$3") (pintype "passive"))
      (node (ref "R22") (pin "2") (pinfunction "2_2") (pintype "passive"))
    )
    (net (code "63") (name "Net-(Q10-G)") (class "Default")
      (node (ref "Q10") (pin "P$1") (pinfunction "G_P$1") (pintype "passive"))
      (node (ref "R10") (pin "1") (pinfunction "1_1") (pintype "passive"))
    )
    (net (code "64") (name "Net-(Q10-S)") (class "Default")
      (node (ref "CON1") (pin "4") (pinfunction "4_4") (pintype "passive"))
      (node (ref "Q10") (pin "P$2") (pinfunction "S_P$2") (pintype "passive"))
      (node (ref "R21") (pin "1") (pinfunction "1_1") (pintype "passive"))
      (node (ref "R33") (pin "1") (pinfunction "1_1") (pintype "passive"))
      (node (ref "R46") (pin "1") (pinfunction "1_1") (pintype "passive"))
    )
    (net (code "65") (name "Net-(Q11-D)") (class "Default")
      (node (ref "LED2") (pin "A") (pinfunction "A_A") (pintype "passive"))
      (node (ref "Q11") (pin "P$3") (pinfunction "D_P$3") (pintype "passive"))
      (node (ref "R23") (pin "2") (pinfunction "2_2") (pintype "passive"))
    )
    (net (code "66") (name "Net-(Q11-G)") (class "Default")
      (node (ref "Q11") (pin "P$1") (pinfunction "G_P$1") (pintype "passive"))
      (node (ref "R11") (pin "1") (pinfunction "1_1") (pintype "passive"))
    )
    (net (code "67") (name "Net-(Q11-S)") (class "Default")
      (node (ref "CON1") (pin "3") (pinfunction "3_3") (pintype "passive"))
      (node (ref "Q11") (pin "P$2") (pinfunction "S_P$2") (pintype "passive"))
      (node (ref "R22") (pin "1") (pinfunction "1_1") (pintype "passive"))
      (node (ref "R34") (pin "1") (pinfunction "1_1") (pintype "passive"))
      (node (ref "R47") (pin "1") (pinfunction "1_1") (pintype "passive"))
    )
    (net (code "68") (name "Net-(Q12-D)") (class "Default")
      (node (ref "LED1") (pin "A") (pinfunction "A_A") (pintype "passive"))
      (node (ref "Q12") (pin "P$3") (pinfunction "D_P$3") (pintype "passive"))
      (node (ref "R24") (pin "2") (pinfunction "2_2") (pintype "passive"))
    )
    (net (code "69") (name "Net-(Q12-G)") (class "Default")
      (node (ref "Q12") (pin "P$1") (pinfunction "G_P$1") (pintype "passive"))
      (node (ref "R12") (pin "1") (pinfunction "1_1") (pintype "passive"))
    )
    (net (code "70") (name "Net-(Q12-S)") (class "Default")
      (node (ref "CON1") (pin "2") (pinfunction "2_2") (pintype "passive"))
      (node (ref "Q12") (pin "P$2") (pinfunction "S_P$2") (pintype "passive"))
      (node (ref "R23") (pin "1") (pinfunction "1_1") (pintype "passive"))
      (node (ref "R35") (pin "1") (pinfunction "1_1") (pintype "passive"))
      (node (ref "R48") (pin "1") (pinfunction "1_1") (pintype "passive"))
    )
    (net (code "71") (name "Net-(U1-+VBAT)") (class "Default")
      (node (ref "C16") (pin "1") (pinfunction "1_1") (pintype "passive"))
      (node (ref "R58") (pin "2") (pinfunction "2_2") (pintype "passive"))
      (node (ref "U1") (pin "P1") (pinfunction "+VBAT_P1") (pintype "passive"))
    )
    (net (code "72") (name "Net-(U1-A0)") (class "Default")
      (node (ref "J1") (pin "2") (pinfunction "2_2") (pintype "passive"))
      (node (ref "U1") (pin "P37") (pinfunction "A0_P37") (pintype "passive"))
    )
    (net (code "73") (name "Net-(U1-A1)") (class "Default")
      (node (ref "J2") (pin "2") (pinfunction "2_2") (pintype "passive"))
      (node (ref "U1") (pin "P38") (pinfunction "A1_P38") (pintype "passive"))
    )
    (net (code "74") (name "Net-(U1-A2)") (class "Default")
      (node (ref "J3") (pin "2") (pinfunction "2_2") (pintype "passive"))
      (node (ref "U1") (pin "P39") (pinfunction "A2_P39") (pintype "passive"))
    )
    (net (code "75") (name "Net-(U1-A3)") (class "Default")
      (node (ref "J4") (pin "2") (pinfunction "2_2") (pintype "passive"))
      (node (ref "U1") (pin "P40") (pinfunction "A3_P40") (pintype "passive"))
    )
    (net (code "76") (name "Net-(U1-S1)") (class "Default")
      (node (ref "R12") (pin "2") (pinfunction "2_2") (pintype "passive"))
      (node (ref "U1") (pin "P25") (pinfunction "S1_P25") (pintype "passive"))
    )
    (net (code "77") (name "Net-(U1-S2)") (class "Default")
      (node (ref "R11") (pin "2") (pinfunction "2_2") (pintype "passive"))
      (node (ref "U1") (pin "P23") (pinfunction "S2_P23") (pintype "passive"))
    )
    (net (code "78") (name "Net-(U1-S3)") (class "Default")
      (node (ref "R10") (pin "2") (pinfunction "2_2") (pintype "passive"))
      (node (ref "U1") (pin "P21") (pinfunction "S3_P21") (pintype "passive"))
    )
    (net (code "79") (name "Net-(U1-S4)") (class "Default")
      (node (ref "R9") (pin "2") (pinfunction "2_2") (pintype "passive"))
      (node (ref "U1") (pin "P19") (pinfunction "S4_P19") (pintype "passive"))
    )
    (net (code "80") (name "Net-(U1-S5)") (class "Default")
      (node (ref "R8") (pin "2") (pinfunction "2_2") (pintype "passive"))
      (node (ref "U1") (pin "P17") (pinfunction "S5_P17") (pintype "passive"))
    )
    (net (code "81") (name "Net-(U1-S6)") (class "Default")
      (node (ref "R7") (pin "2") (pinfunction "2_2") (pintype "passive"))
      (node (ref "U1") (pin "P15") (pinfunction "S6_P15") (pintype "passive"))
    )
    (net (code "82") (name "Net-(U1-S7)") (class "Default")
      (node (ref "R6") (pin "2") (pinfunction "2_2") (pintype "passive"))
      (node (ref "U1") (pin "P13") (pinfunction "S7_P13") (pintype "passive"))
    )
    (net (code "83") (name "Net-(U1-S8)") (class "Default")
      (node (ref "R5") (pin "2") (pinfunction "2_2") (pintype "passive"))
      (node (ref "U1") (pin "P11") (pinfunction "S8_P11") (pintype "passive"))
    )
    (net (code "84") (name "Net-(U1-S9)") (class "Default")
      (node (ref "R4") (pin "2") (pinfunction "2_2") (pintype "passive"))
      (node (ref "U1") (pin "P9") (pinfunction "S9_P9") (pintype "passive"))
    )
    (net (code "85") (name "Net-(U1-S10)") (class "Default")
      (node (ref "R3") (pin "2") (pinfunction "2_2") (pintype "passive"))
      (node (ref "U1") (pin "P7") (pinfunction "S10_P7") (pintype "passive"))
    )
    (net (code "86") (name "Net-(U1-S11)") (class "Default")
      (node (ref "R2") (pin "2") (pinfunction "2_2") (pintype "passive"))
      (node (ref "U1") (pin "P5") (pinfunction "S11_P5") (pintype "passive"))
    )
    (net (code "87") (name "Net-(U1-S12)") (class "Default")
      (node (ref "R1") (pin "2") (pinfunction "2_2") (pintype "passive"))
      (node (ref "U1") (pin "P3") (pinfunction "S12_P3") (pintype "passive"))
    )
    (net (code "88") (name "Net-(U1-SCKL)") (class "Default")
      (node (ref "U1") (pin "P41") (pinfunction "SCKL_P41") (pintype "passive"))
      (node (ref "U2") (pin "14") (pinfunction "VOA_14") (pintype "passive"))
    )
    (net (code "89") (name "Net-(U1-SDI)") (class "Default")
      (node (ref "U1") (pin "P42") (pinfunction "SDI_P42") (pintype "passive"))
      (node (ref "U2") (pin "13") (pinfunction "VOB_13") (pintype "passive"))
    )
    (net (code "90") (name "Net-(U1-SDO)") (class "Default")
      (node (ref "R49") (pin "1") (pinfunction "1_1") (pintype "passive"))
      (node (ref "U1") (pin "P43") (pinfunction "SDO_P43") (pintype "passive"))
      (node (ref "U2") (pin "11") (pinfunction "VID_11") (pintype "passive"))
    )
    (net (code "91") (name "Net-(U1-VREF)") (class "Default")
      (node (ref "C13") (pin "1") (pinfunction "1_1") (pintype "passive"))
      (node (ref "R56") (pin "2") (pinfunction "2_2") (pintype "passive"))
      (node (ref "R57") (pin "2") (pinfunction "2_2") (pintype "passive"))
      (node (ref "U1") (pin "P31") (pinfunction "VREF_P31") (pintype "passive"))
    )
    (net (code "92") (name "Net-(U1-VTEMP1)") (class "Default")
      (node (ref "CON2") (pin "4") (pinfunction "4_4") (pintype "passive"))
      (node (ref "R56") (pin "1") (pinfunction "1_1") (pintype "passive"))
      (node (ref "U1") (pin "P29") (pinfunction "VTEMP1_P29") (pintype "passive"))
    )
    (net (code "93") (name "Net-(U1-VTEMP2)") (class "Default")
      (node (ref "CON2") (pin "2") (pinfunction "2_2") (pintype "passive"))
      (node (ref "R57") (pin "1") (pinfunction "1_1") (pintype "passive"))
      (node (ref "U1") (pin "P30") (pinfunction "VTEMP2_P30") (pintype "passive"))
    )
    (net (code "94") (name "Net-(U1-~{CSBI})") (class "Default")
      (node (ref "U1") (pin "P44") (pinfunction "~{CSBI}_P44") (pintype "passive"))
      (node (ref "U2") (pin "12") (pinfunction "VOC_12") (pintype "passive"))
    )
    (net (code "95") (name "Net-(U2-VOD)") (class "Default")
      (node (ref "D18") (pin "C") (pinfunction "C_C") (pintype "passive"))
      (node (ref "U2") (pin "6") (pinfunction "VOD_6") (pintype "passive"))
    )
    (net (code "96") (name "unconnected-(U2-CTRL1-Pad7)") (class "Default")
      (node (ref "U2") (pin "7") (pinfunction "CTRL1_7") (pintype "passive"))
    )
    (net (code "97") (name "unconnected-(U2-CTRL2-Pad10)") (class "Default")
      (node (ref "U2") (pin "10") (pinfunction "CTRL2_10") (pintype "passive"))
    )
  )
)
